# shared_name_label.net
KiCad netlist of a schematic drawn in Altium Designer
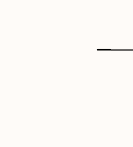
[diagram p0: shared_name_label.SchDoc, top left]
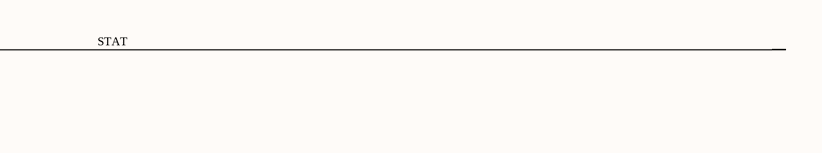
[diagram p1: shared_name_label.SchDoc, top right]
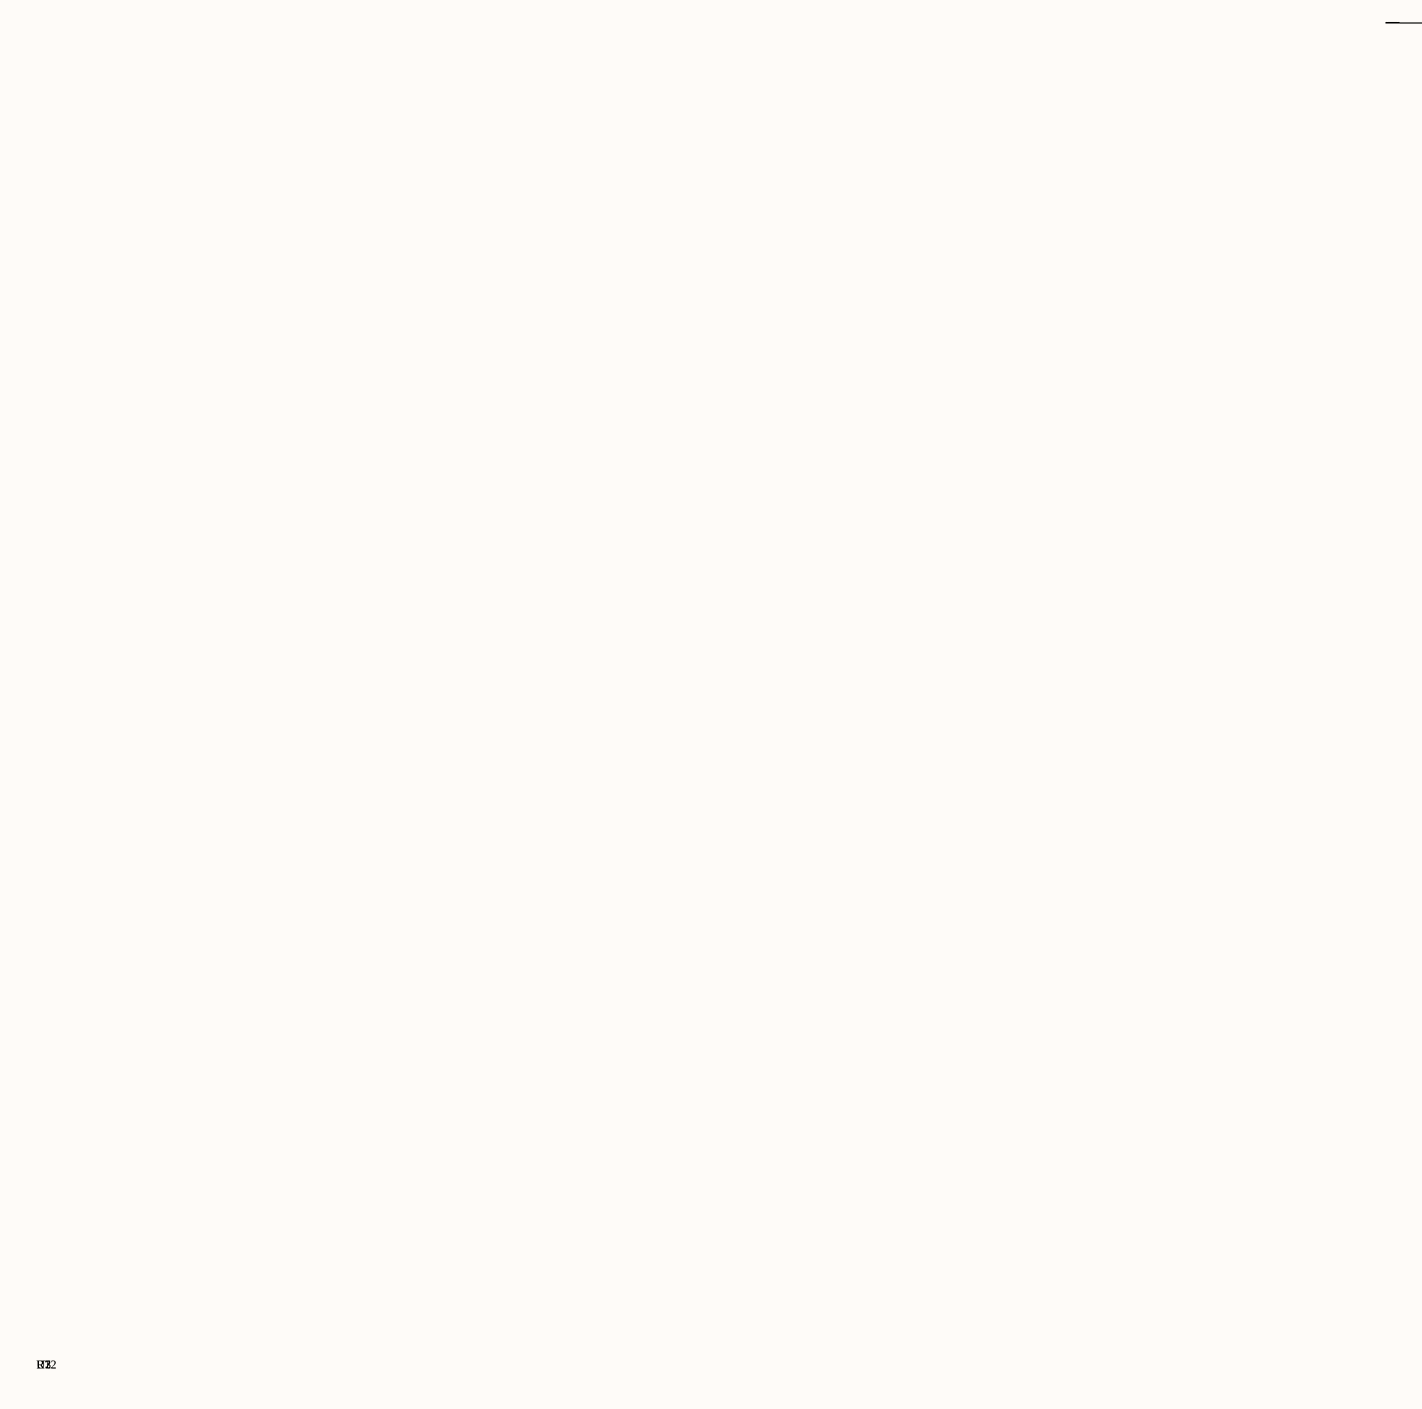
[diagram p2: shared_name_label.SchDoc, bottom left]
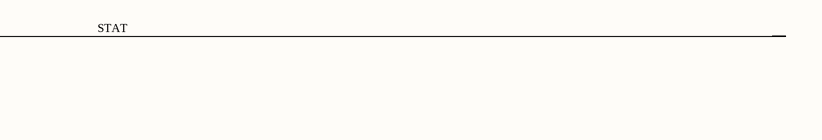
[diagram p3: shared_name_label.SchDoc, bottom right]

(export (version "E")
  (design (tool "Eeschema 10.0.6"))
  (components
    (comp (ref "R7") (value "~") (libsource (lib "") (part "root_0_DEVICE__1")))
    (comp (ref "R12") (value "~") (libsource (lib "") (part "root_0_DEVICE__3")))
    (comp (ref "U2") (value "~") (libsource (lib "altium-import") (part "root_0_DEVICE_")))
    (comp (ref "U3") (value "~") (libsource (lib "") (part "root_0_DEVICE__2")))
  )
  (nets
    (net (code "1") (name "/STAT") (class "Default")
      (node (ref "R12") (pin "1") (pinfunction "B_1") (pintype "passive"))
      (node (ref "R7") (pin "1") (pinfunction "A_1") (pintype "passive"))
      (node (ref "U2") (pin "1") (pinfunction "STAT_1") (pintype "passive"))
      (node (ref "U3") (pin "2") (pinfunction "LED_2") (pintype "passive"))
    )
  )
)
